# KidSize.net
KiCad netlist of a schematic drawn in EAGLE
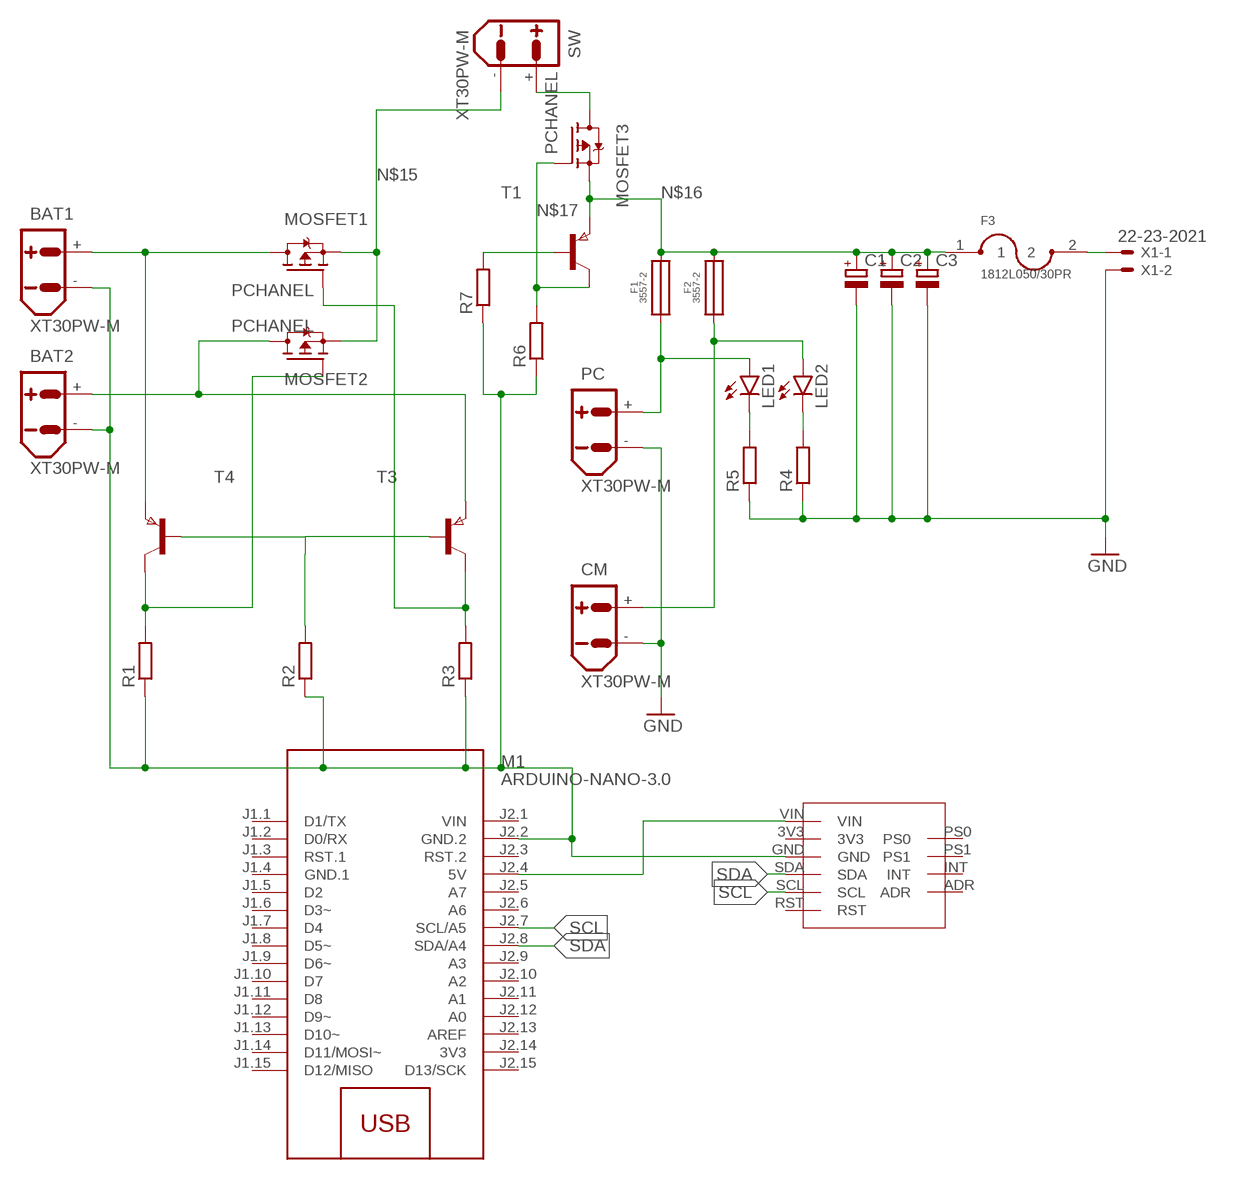
[diagram p0: schematic, sheet 1]

(export (version "E")
  (design (tool "Eeschema 10.0.6"))
  (components
    (comp (ref "BAT1")
      (value "XT30PW-M")
      (footprint "eagle-import:XT30PW-M")
      (libsource (lib "eagle-import") (part "XT30PW-M"))
    )
    (comp (ref "BAT2")
      (value "XT30PW-M")
      (footprint "eagle-import:XT30PW-M")
      (libsource (lib "eagle-import") (part "XT30PW-M"))
    )
    (comp (ref "C1")
      (value "CPOL-EU150CLZ-1014")
      (footprint "eagle-import:150CLZ-1014")
      (libsource (lib "eagle-import") (part "CPOL-EU150CLZ-1014"))
    )
    (comp (ref "C2")
      (value "CPOL-EU150CLZ-1014")
      (footprint "eagle-import:150CLZ-1014")
      (libsource (lib "eagle-import") (part "CPOL-EU150CLZ-1014"))
    )
    (comp (ref "C3")
      (value "CPOL-EU150CLZ-1014")
      (footprint "eagle-import:150CLZ-1014")
      (libsource (lib "eagle-import") (part "CPOL-EU150CLZ-1014"))
    )
    (comp (ref "CM")
      (value "XT30PW-M")
      (footprint "eagle-import:XT30PW-M")
      (libsource (lib "eagle-import") (part "XT30PW-M"))
    )
    (comp (ref "F1")
      (value "3557-2")
      (footprint "eagle-import:3557-2")
      (libsource (lib "eagle-import") (part "3557-2"))
    )
    (comp (ref "F2")
      (value "3557-2")
      (footprint "eagle-import:3557-2")
      (libsource (lib "eagle-import") (part "3557-2"))
    )
    (comp (ref "F3")
      (value "1812L050/30PR")
      (footprint "eagle-import:FUSM4632X75")
      (fields (field (name "MF") "Littelfuse"))
      (libsource (lib "eagle-import") (part "1812L050/30PR"))
    )
    (comp (ref "LED1")
      (value "LEDCHIP-LED0805")
      (footprint "eagle-import:CHIP-LED0805")
      (libsource (lib "eagle-import") (part "LEDCHIP-LED0805"))
    )
    (comp (ref "LED2")
      (value "LEDCHIP-LED0805")
      (footprint "eagle-import:CHIP-LED0805")
      (libsource (lib "eagle-import") (part "LEDCHIP-LED0805"))
    )
    (comp (ref "M1")
      (value "ARDUINO-NANO-3.0")
      (footprint "eagle-import:ARDUINO-NANO-3.0")
      (libsource (lib "eagle-import") (part "ARDUINO-NANO-3.0"))
    )
    (comp (ref "MOSFET1")
      (value "PCHANEL")
      (footprint "eagle-import:TO252")
      (libsource (lib "eagle-import") (part "FDD4141TO252"))
    )
    (comp (ref "MOSFET2")
      (value "PCHANEL")
      (footprint "eagle-import:TO252")
      (libsource (lib "eagle-import") (part "FDD4141TO252"))
    )
    (comp (ref "MOSFET3")
      (value "PCHANEL")
      (footprint "eagle-import:TO252")
      (libsource (lib "eagle-import") (part "FDD4141TO252"))
    )
    (comp (ref "PC")
      (value "XT30PW-M")
      (footprint "eagle-import:XT30PW-M")
      (libsource (lib "eagle-import") (part "XT30PW-M"))
    )
    (comp (ref "R1")
      (value "R-EU_R1206")
      (footprint "eagle-import:R1206")
      (libsource (lib "eagle-import") (part "R-EU_R1206"))
    )
    (comp (ref "R2")
      (value "R-EU_R1206")
      (footprint "eagle-import:R1206")
      (libsource (lib "eagle-import") (part "R-EU_R1206"))
    )
    (comp (ref "R3")
      (value "R-EU_R1206")
      (footprint "eagle-import:R1206")
      (libsource (lib "eagle-import") (part "R-EU_R1206"))
    )
    (comp (ref "R4")
      (value "R-EU_M0805")
      (footprint "eagle-import:M0805")
      (libsource (lib "eagle-import") (part "R-EU_M0805"))
    )
    (comp (ref "R5")
      (value "R-EU_M0805")
      (footprint "eagle-import:M0805")
      (libsource (lib "eagle-import") (part "R-EU_M0805"))
    )
    (comp (ref "R6")
      (value "R-EU_M0805")
      (footprint "eagle-import:M0805")
      (libsource (lib "eagle-import") (part "R-EU_M0805"))
    )
    (comp (ref "R7")
      (value "R-EU_M0805")
      (footprint "eagle-import:M0805")
      (libsource (lib "eagle-import") (part "R-EU_M0805"))
    )
    (comp (ref "SW")
      (value "XT30PW-M")
      (footprint "eagle-import:XT30PW-M")
      (libsource (lib "eagle-import") (part "XT30PW-M"))
    )
    (comp (ref "T1")
      (value "PNPSOT23")
      (footprint "eagle-import:SOT-23")
      (fields (field (name "MPN") "DSS20200L-7"))
      (libsource (lib "eagle-import") (part "PNPSOT23"))
    )
    (comp (ref "T3")
      (value "PNPSOT23")
      (footprint "eagle-import:SOT-23")
      (fields (field (name "MPN") "DSS20200L-7"))
      (libsource (lib "eagle-import") (part "PNPSOT23"))
    )
    (comp (ref "T4")
      (value "PNPSOT23")
      (footprint "eagle-import:SOT-23")
      (fields (field (name "MPN") "DSS20200L-7"))
      (libsource (lib "eagle-import") (part "PNPSOT23"))
    )
    (comp (ref "U$1")
      (value "BNO055_BNO055")
      (footprint "eagle-import:BNO055_BNO055")
      (libsource (lib "eagle-import") (part "BNO055_BNO055"))
    )
    (comp (ref "X1")
      (value "22-23-2021")
      (footprint "eagle-import:22-23-2021")
      (fields (field (name "MF") "MOLEX"))
      (libsource (lib "eagle-import") (part "22-23-2021"))
    )
  )
  (nets
    (net (code "1") (name "/3V3") (class "Default")
      (node (ref "M1") (pin "J2.14") (pinfunction "3V3_J2.14") (pintype "power_in"))
    )
    (net (code "2") (name "/GND.1") (class "Default")
      (node (ref "M1") (pin "J1.4") (pinfunction "GND.1_J1.4") (pintype "power_in"))
    )
    (net (code "3") (name "/N$15") (class "Default")
      (node (ref "MOSFET1") (pin "2") (pinfunction "S_2") (pintype "passive"))
      (node (ref "MOSFET2") (pin "2") (pinfunction "S_2") (pintype "passive"))
      (node (ref "SW") (pin "-") (pinfunction "-_-") (pintype "power_in"))
    )
    (net (code "4") (name "/N$16") (class "Default")
      (node (ref "C1") (pin "+") (pinfunction "+_+") (pintype "passive"))
      (node (ref "C2") (pin "+") (pinfunction "+_+") (pintype "passive"))
      (node (ref "C3") (pin "+") (pinfunction "+_+") (pintype "passive"))
      (node (ref "F1") (pin "3") (pinfunction "2_3") (pintype "bidirectional"))
      (node (ref "F1") (pin "4") (pinfunction "2_4") (pintype "bidirectional"))
      (node (ref "F2") (pin "3") (pinfunction "2_3") (pintype "bidirectional"))
      (node (ref "F2") (pin "4") (pinfunction "2_4") (pintype "bidirectional"))
      (node (ref "F3") (pin "1") (pinfunction "1_1") (pintype "passive"))
      (node (ref "MOSFET3") (pin "2") (pinfunction "S_2") (pintype "passive"))
      (node (ref "T1") (pin "2") (pinfunction "E_2") (pintype "passive"))
    )
    (net (code "5") (name "/N$17") (class "Default")
      (node (ref "MOSFET3") (pin "1") (pinfunction "G_1") (pintype "passive"))
      (node (ref "R6") (pin "2") (pinfunction "2_2") (pintype "passive"))
      (node (ref "T1") (pin "1") (pinfunction "C_1") (pintype "passive"))
    )
    (net (code "6") (name "/VIN") (class "Default")
      (node (ref "M1") (pin "J2.1") (pinfunction "VIN_J2.1") (pintype "power_in"))
    )
    (net (code "7") (name "GND") (class "Default")
      (node (ref "BAT1") (pin "-") (pinfunction "-_-") (pintype "power_in"))
      (node (ref "BAT2") (pin "-") (pinfunction "-_-") (pintype "power_in"))
      (node (ref "C1") (pin "-") (pinfunction "-_-") (pintype "passive"))
      (node (ref "C2") (pin "-") (pinfunction "-_-") (pintype "passive"))
      (node (ref "C3") (pin "-") (pinfunction "-_-") (pintype "passive"))
      (node (ref "CM") (pin "-") (pinfunction "-_-") (pintype "power_in"))
      (node (ref "M1") (pin "J2.2") (pinfunction "GND.2_J2.2") (pintype "power_in"))
      (node (ref "PC") (pin "-") (pinfunction "-_-") (pintype "power_in"))
      (node (ref "R1") (pin "1") (pinfunction "1_1") (pintype "passive"))
      (node (ref "R2") (pin "1") (pinfunction "1_1") (pintype "passive"))
      (node (ref "R3") (pin "1") (pinfunction "1_1") (pintype "passive"))
      (node (ref "R4") (pin "1") (pinfunction "1_1") (pintype "passive"))
      (node (ref "R5") (pin "1") (pinfunction "1_1") (pintype "passive"))
      (node (ref "R6") (pin "1") (pinfunction "1_1") (pintype "passive"))
      (node (ref "R7") (pin "1") (pinfunction "1_1") (pintype "passive"))
      (node (ref "U$1") (pin "GND") (pinfunction "GND_GND") (pintype "bidirectional"))
      (node (ref "X1") (pin "2") (pinfunction "S_2") (pintype "passive"))
    )
    (net (code "8") (name "Net-(CM-Pad+)") (class "Default")
      (node (ref "CM") (pin "+") (pinfunction "+_+") (pintype "power_in"))
      (node (ref "F2") (pin "1") (pinfunction "1_1") (pintype "bidirectional"))
      (node (ref "F2") (pin "2") (pinfunction "1_2") (pintype "bidirectional"))
      (node (ref "LED2") (pin "A") (pinfunction "A_A") (pintype "passive"))
    )
    (net (code "9") (name "Net-(F1-1-Pad2)") (class "Default")
      (node (ref "F1") (pin "1") (pinfunction "1_1") (pintype "bidirectional"))
      (node (ref "F1") (pin "2") (pinfunction "1_2") (pintype "bidirectional"))
      (node (ref "LED1") (pin "A") (pinfunction "A_A") (pintype "passive"))
      (node (ref "PC") (pin "+") (pinfunction "+_+") (pintype "power_in"))
    )
    (net (code "10") (name "Net-(LED1-PadC)") (class "Default")
      (node (ref "LED1") (pin "C") (pinfunction "C_C") (pintype "passive"))
      (node (ref "R5") (pin "2") (pinfunction "2_2") (pintype "passive"))
    )
    (net (code "11") (name "Net-(LED2-PadC)") (class "Default")
      (node (ref "LED2") (pin "C") (pinfunction "C_C") (pintype "passive"))
      (node (ref "R4") (pin "2") (pinfunction "2_2") (pintype "passive"))
    )
    (net (code "12") (name "Net-(M1-5V)") (class "Default")
      (node (ref "M1") (pin "J2.4") (pinfunction "5V_J2.4") (pintype "power_in"))
      (node (ref "U$1") (pin "VIN") (pinfunction "VIN_VIN") (pintype "bidirectional"))
    )
    (net (code "13") (name "Net-(MOSFET1-D)") (class "Default")
      (node (ref "BAT1") (pin "+") (pinfunction "+_+") (pintype "power_in"))
      (node (ref "MOSFET1") (pin "3") (pinfunction "D_3") (pintype "passive"))
      (node (ref "T4") (pin "2") (pinfunction "E_2") (pintype "passive"))
    )
    (net (code "14") (name "Net-(MOSFET1-G)") (class "Default")
      (node (ref "MOSFET1") (pin "1") (pinfunction "G_1") (pintype "passive"))
      (node (ref "R3") (pin "2") (pinfunction "2_2") (pintype "passive"))
      (node (ref "T3") (pin "1") (pinfunction "C_1") (pintype "passive"))
    )
    (net (code "15") (name "Net-(MOSFET2-D)") (class "Default")
      (node (ref "BAT2") (pin "+") (pinfunction "+_+") (pintype "power_in"))
      (node (ref "MOSFET2") (pin "3") (pinfunction "D_3") (pintype "passive"))
      (node (ref "T3") (pin "2") (pinfunction "E_2") (pintype "passive"))
    )
    (net (code "16") (name "Net-(MOSFET2-G)") (class "Default")
      (node (ref "MOSFET2") (pin "1") (pinfunction "G_1") (pintype "passive"))
      (node (ref "R1") (pin "2") (pinfunction "2_2") (pintype "passive"))
      (node (ref "T4") (pin "1") (pinfunction "C_1") (pintype "passive"))
    )
    (net (code "17") (name "Net-(MOSFET3-D)") (class "Default")
      (node (ref "MOSFET3") (pin "3") (pinfunction "D_3") (pintype "passive"))
      (node (ref "SW") (pin "+") (pinfunction "+_+") (pintype "power_in"))
    )
    (net (code "18") (name "Net-(T1-B)") (class "Default")
      (node (ref "R7") (pin "2") (pinfunction "2_2") (pintype "passive"))
      (node (ref "T1") (pin "3") (pinfunction "B_3") (pintype "passive"))
    )
    (net (code "19") (name "Net-(T3-B)") (class "Default")
      (node (ref "R2") (pin "2") (pinfunction "2_2") (pintype "passive"))
      (node (ref "T3") (pin "3") (pinfunction "B_3") (pintype "passive"))
      (node (ref "T4") (pin "3") (pinfunction "B_3") (pintype "passive"))
    )
    (net (code "20") (name "Net-(X1A-S)") (class "Default")
      (node (ref "F3") (pin "2") (pinfunction "2_2") (pintype "passive"))
      (node (ref "X1") (pin "1") (pinfunction "S_1") (pintype "passive"))
    )
    (net (code "21") (name "SCL") (class "Default")
      (node (ref "M1") (pin "J2.7") (pinfunction "SCL/A5_J2.7") (pintype "bidirectional"))
      (node (ref "U$1") (pin "SCL") (pinfunction "SCL_SCL") (pintype "bidirectional"))
    )
    (net (code "22") (name "SDA") (class "Default")
      (node (ref "M1") (pin "J2.8") (pinfunction "SDA/A4_J2.8") (pintype "bidirectional"))
      (node (ref "U$1") (pin "SDA") (pinfunction "SDA_SDA") (pintype "bidirectional"))
    )
    (net (code "23") (name "unconnected-(M1-A0-PadJ2.12)") (class "Default")
      (node (ref "M1") (pin "J2.12") (pinfunction "A0_J2.12") (pintype "bidirectional"))
    )
    (net (code "24") (name "unconnected-(M1-A1-PadJ2.11)") (class "Default")
      (node (ref "M1") (pin "J2.11") (pinfunction "A1_J2.11") (pintype "bidirectional"))
    )
    (net (code "25") (name "unconnected-(M1-A2-PadJ2.10)") (class "Default")
      (node (ref "M1") (pin "J2.10") (pinfunction "A2_J2.10") (pintype "bidirectional"))
    )
    (net (code "26") (name "unconnected-(M1-A3-PadJ2.9)") (class "Default")
      (node (ref "M1") (pin "J2.9") (pinfunction "A3_J2.9") (pintype "bidirectional"))
    )
    (net (code "27") (name "unconnected-(M1-A6-PadJ2.6)") (class "Default")
      (node (ref "M1") (pin "J2.6") (pinfunction "A6_J2.6") (pintype "bidirectional"))
    )
    (net (code "28") (name "unconnected-(M1-A7-PadJ2.5)") (class "Default")
      (node (ref "M1") (pin "J2.5") (pinfunction "A7_J2.5") (pintype "bidirectional"))
    )
    (net (code "29") (name "unconnected-(M1-AREF-PadJ2.13)") (class "Default")
      (node (ref "M1") (pin "J2.13") (pinfunction "AREF_J2.13") (pintype "bidirectional"))
    )
    (net (code "30") (name "unconnected-(M1-D0{slash}RX-PadJ1.2)") (class "Default")
      (node (ref "M1") (pin "J1.2") (pinfunction "D0/RX_J1.2") (pintype "bidirectional"))
    )
    (net (code "31") (name "unconnected-(M1-D1{slash}TX-PadJ1.1)") (class "Default")
      (node (ref "M1") (pin "J1.1") (pinfunction "D1/TX_J1.1") (pintype "bidirectional"))
    )
    (net (code "32") (name "unconnected-(M1-D2-PadJ1.5)") (class "Default")
      (node (ref "M1") (pin "J1.5") (pinfunction "D2_J1.5") (pintype "bidirectional"))
    )
    (net (code "33") (name "unconnected-(M1-D3~{}-PadJ1.6)") (class "Default")
      (node (ref "M1") (pin "J1.6") (pinfunction "D3~{}_J1.6") (pintype "bidirectional"))
    )
    (net (code "34") (name "unconnected-(M1-D4-PadJ1.7)") (class "Default")
      (node (ref "M1") (pin "J1.7") (pinfunction "D4_J1.7") (pintype "bidirectional"))
    )
    (net (code "35") (name "unconnected-(M1-D5~{}-PadJ1.8)") (class "Default")
      (node (ref "M1") (pin "J1.8") (pinfunction "D5~{}_J1.8") (pintype "bidirectional"))
    )
    (net (code "36") (name "unconnected-(M1-D6~{}-PadJ1.9)") (class "Default")
      (node (ref "M1") (pin "J1.9") (pinfunction "D6~{}_J1.9") (pintype "bidirectional"))
    )
    (net (code "37") (name "unconnected-(M1-D7-PadJ1.10)") (class "Default")
      (node (ref "M1") (pin "J1.10") (pinfunction "D7_J1.10") (pintype "bidirectional"))
    )
    (net (code "38") (name "unconnected-(M1-D8-PadJ1.11)") (class "Default")
      (node (ref "M1") (pin "J1.11") (pinfunction "D8_J1.11") (pintype "bidirectional"))
    )
    (net (code "39") (name "unconnected-(M1-D9~{}-PadJ1.12)") (class "Default")
      (node (ref "M1") (pin "J1.12") (pinfunction "D9~{}_J1.12") (pintype "bidirectional"))
    )
    (net (code "40") (name "unconnected-(M1-D10~{}-PadJ1.13)") (class "Default")
      (node (ref "M1") (pin "J1.13") (pinfunction "D10~{}_J1.13") (pintype "bidirectional"))
    )
    (net (code "41") (name "unconnected-(M1-D11{slash}MOSI~{}-PadJ1.14)") (class "Default")
      (node (ref "M1") (pin "J1.14") (pinfunction "D11/MOSI~{}_J1.14") (pintype "bidirectional"))
    )
    (net (code "42") (name "unconnected-(M1-D12{slash}MISO-PadJ1.15)") (class "Default")
      (node (ref "M1") (pin "J1.15") (pinfunction "D12/MISO_J1.15") (pintype "bidirectional"))
    )
    (net (code "43") (name "unconnected-(M1-D13{slash}SCK-PadJ2.15)") (class "Default")
      (node (ref "M1") (pin "J2.15") (pinfunction "D13/SCK_J2.15") (pintype "bidirectional"))
    )
    (net (code "44") (name "unconnected-(M1-RST.1-PadJ1.3)") (class "Default")
      (node (ref "M1") (pin "J1.3") (pinfunction "RST.1_J1.3") (pintype "bidirectional"))
    )
    (net (code "45") (name "unconnected-(M1-RST.2-PadJ2.3)") (class "Default")
      (node (ref "M1") (pin "J2.3") (pinfunction "RST.2_J2.3") (pintype "bidirectional"))
    )
    (net (code "46") (name "unconnected-(U$1-Pad3V3)") (class "Default")
      (node (ref "U$1") (pin "3V3") (pinfunction "3V3_3V3") (pintype "bidirectional"))
    )
    (net (code "47") (name "unconnected-(U$1-PadADR)") (class "Default")
      (node (ref "U$1") (pin "ADR") (pinfunction "ADR_ADR") (pintype "bidirectional"))
    )
    (net (code "48") (name "unconnected-(U$1-PadINT)") (class "Default")
      (node (ref "U$1") (pin "INT") (pinfunction "INT_INT") (pintype "bidirectional"))
    )
    (net (code "49") (name "unconnected-(U$1-PadPS0)") (class "Default")
      (node (ref "U$1") (pin "PS0") (pinfunction "PS0_PS0") (pintype "bidirectional"))
    )
    (net (code "50") (name "unconnected-(U$1-PadPS1)") (class "Default")
      (node (ref "U$1") (pin "PS1") (pinfunction "PS1_PS1") (pintype "bidirectional"))
    )
    (net (code "51") (name "unconnected-(U$1-PadRST)") (class "Default")
      (node (ref "U$1") (pin "RST") (pinfunction "RST_RST") (pintype "bidirectional"))
    )
  )
)
